# USART.net
KiCad netlist of a schematic drawn in Altium Designer
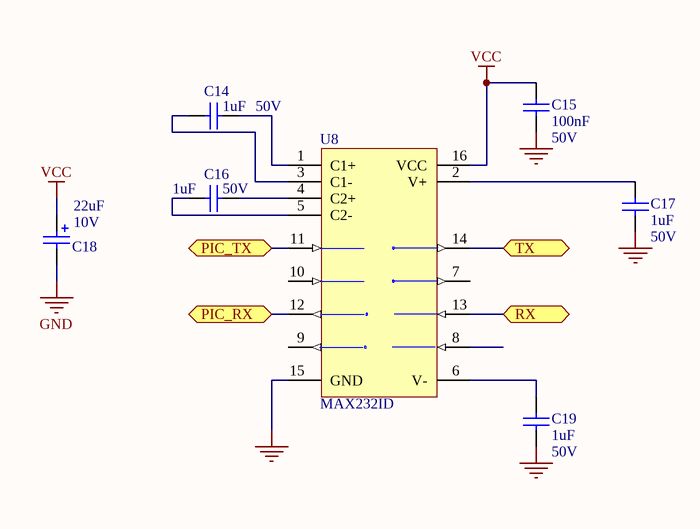
[diagram p0: USART.SchDoc]

(export (version "E")
  (design (tool "Eeschema 10.0.6"))
  (components
    (comp (ref "C14")
      (value "1uF")
      (footprint "3-0603_L")
      (description "Capacitor")
      (fields
        (field (name "VOLTAGE") "50V")
        (field (name "Comment") "Cap")
        (field (name "PUBLISHER") "Altium Limited")
      )
      (libsource (lib "Erdem_05112012") (part "Cap"))
    )
    (comp (ref "C15")
      (value "100nF")
      (footprint "3-0603_L")
      (description "Capacitor")
      (fields
        (field (name "VOLTAGE") "50V")
        (field (name "Comment") "Cap")
        (field (name "PUBLISHER") "Altium Limited")
      )
      (libsource (lib "Erdem_05112012") (part "Cap"))
    )
    (comp (ref "C16")
      (value "1uF")
      (footprint "3-0603_L")
      (description "Capacitor")
      (fields
        (field (name "VOLTAGE") "50V")
        (field (name "Comment") "Cap")
        (field (name "PUBLISHER") "Altium Limited")
      )
      (libsource (lib "Erdem_05112012") (part "Cap"))
    )
    (comp (ref "C17")
      (value "1uF")
      (footprint "3-0603_L")
      (description "Capacitor")
      (fields
        (field (name "VOLTAGE") "50V")
        (field (name "Comment") "Cap")
        (field (name "PUBLISHER") "Altium Limited")
      )
      (libsource (lib "Erdem_05112012") (part "Cap"))
    )
    (comp (ref "C18")
      (value "22uF")
      (footprint "3528")
      (fields
        (field (name "VOLTAGE") "10V")
        (field (name "Comment") "CAP-Tantal")
        (field (name "PUBLISHER") "Altium Limited")
      )
      (libsource (lib "Erdem_05112012") (part "CAP-Tantal"))
    )
    (comp (ref "C19")
      (value "1uF")
      (footprint "3-0603_L")
      (description "Capacitor")
      (fields
        (field (name "VOLTAGE") "50V")
        (field (name "Comment") "Cap")
        (field (name "PUBLISHER") "Altium Limited")
      )
      (libsource (lib "Erdem_05112012") (part "Cap"))
    )
    (comp (ref "U8")
      (value "MAX232ID")
      (footprint "SOIC16 - big")
      (description "5V, Low-Power, up to 1Mbps, True RS-232 Transceiver Using Four 0.1µF External Capacitor")
      (fields (field (name "PUBLISHER") "Altium Limited"))
      (libsource (lib "Erdem_05112012") (part "MAX232ID"))
    )
  )
  (nets
    (net (code "1") (name "/PIC_RX") (class "Default")
      (node (ref "U8") (pin "12") (pinfunction "R1OUT_12") (pintype "output"))
    )
    (net (code "2") (name "/PIC_TX") (class "Default")
      (node (ref "U8") (pin "11") (pinfunction "T1IN_11") (pintype "input"))
    )
    (net (code "3") (name "/RX") (class "Default")
      (node (ref "U8") (pin "13") (pinfunction "R1IN_13") (pintype "input"))
    )
    (net (code "4") (name "/TX") (class "Default")
      (node (ref "U8") (pin "14") (pinfunction "T1OUT_14") (pintype "output"))
    )
    (net (code "5") (name "GND") (class "Default")
      (node (ref "C15") (pin "1") (pinfunction "1_1") (pintype "passive"))
      (node (ref "C17") (pin "1") (pinfunction "1_1") (pintype "passive"))
      (node (ref "C18") (pin "2") (pinfunction "2_2") (pintype "passive"))
      (node (ref "C19") (pin "1") (pinfunction "1_1") (pintype "passive"))
      (node (ref "U8") (pin "15") (pinfunction "GND_15") (pintype "power_in"))
    )
    (net (code "6") (name "Net-(U8-C1+)") (class "Default")
      (node (ref "C14") (pin "1") (pinfunction "1_1") (pintype "passive"))
      (node (ref "U8") (pin "1") (pinfunction "C1+_1") (pintype "passive"))
    )
    (net (code "7") (name "Net-(U8-C1-)") (class "Default")
      (node (ref "C14") (pin "2") (pinfunction "2_2") (pintype "passive"))
      (node (ref "U8") (pin "3") (pinfunction "C1-_3") (pintype "passive"))
    )
    (net (code "8") (name "Net-(U8-C2+)") (class "Default")
      (node (ref "C16") (pin "1") (pinfunction "1_1") (pintype "passive"))
      (node (ref "U8") (pin "4") (pinfunction "C2+_4") (pintype "passive"))
    )
    (net (code "9") (name "Net-(U8-C2-)") (class "Default")
      (node (ref "C16") (pin "2") (pinfunction "2_2") (pintype "passive"))
      (node (ref "U8") (pin "5") (pinfunction "C2-_5") (pintype "passive"))
    )
    (net (code "10") (name "Net-(U8-V+)") (class "Default")
      (node (ref "C17") (pin "2") (pinfunction "2_2") (pintype "passive"))
      (node (ref "U8") (pin "2") (pinfunction "V+_2") (pintype "power_in"))
    )
    (net (code "11") (name "Net-(U8-V-)") (class "Default")
      (node (ref "C19") (pin "2") (pinfunction "2_2") (pintype "passive"))
      (node (ref "U8") (pin "6") (pinfunction "V-_6") (pintype "power_in"))
    )
    (net (code "12") (name "VCC") (class "Default")
      (node (ref "C15") (pin "2") (pinfunction "2_2") (pintype "passive"))
      (node (ref "C18") (pin "1") (pinfunction "1_1") (pintype "passive"))
      (node (ref "U8") (pin "16") (pinfunction "VCC_16") (pintype "power_in"))
    )
    (net (code "13") (name "unconnected-(U8-R2IN-Pad8)") (class "Default")
      (node (ref "U8") (pin "8") (pinfunction "R2IN_8") (pintype "input"))
    )
    (net (code "14") (name "unconnected-(U8-R2OUT-Pad9)") (class "Default")
      (node (ref "U8") (pin "9") (pinfunction "R2OUT_9") (pintype "output"))
    )
    (net (code "15") (name "unconnected-(U8-T2IN-Pad10)") (class "Default")
      (node (ref "U8") (pin "10") (pinfunction "T2IN_10") (pintype "input"))
    )
    (net (code "16") (name "unconnected-(U8-T2OUT-Pad7)") (class "Default")
      (node (ref "U8") (pin "7") (pinfunction "T2OUT_7") (pintype "output"))
    )
  )
)
